# Main.net
KiCad netlist of a schematic drawn in Altium Designer
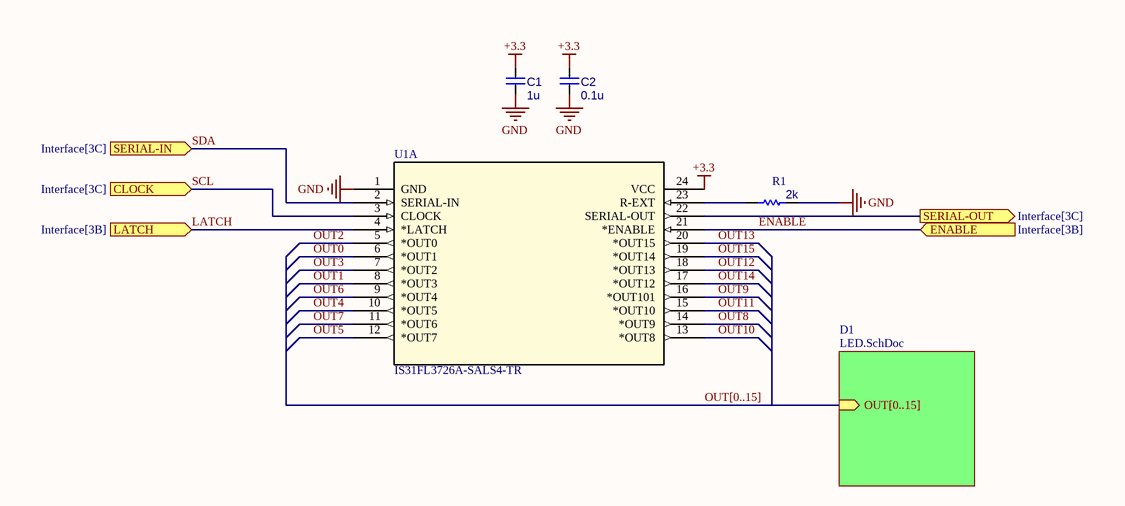
[diagram p0: Main.SchDoc]

(export (version "E")
  (design (tool "Eeschema 10.0.6"))
  (components
    (comp (ref "C1")
      (value "1u")
      (footprint "C0603B")
      (description "Non-polarized capacitor")
      (fields (field (name "Comment") "Capacitor"))
      (libsource (lib "Space Concordia") (part "Capacitor"))
    )
    (comp (ref "C2")
      (value "0.1u")
      (footprint "C0603B")
      (description "Non-polarized capacitor")
      (fields (field (name "Comment") "Capacitor"))
      (libsource (lib "Space Concordia") (part "Capacitor"))
    )
    (comp (ref "R1")
      (value "2k")
      (footprint "R0603B")
      (description "Resistor")
      (libsource (lib "Space Concordia") (part "Resistor"))
    )
    (comp (ref "U1")
      (value "IS31FL3726A-SALS4-TR")
      (footprint "SSOP-24_LMS")
      (description "LED Driver IC 16 Output Linear Shift Register No Dimming 25.2mA 24-eTSSOP")
      (libsource (lib "Space Concordia") (part "IS31FL3726A-SALS4-TR"))
    )
  )
  (nets
    (net (code "1") (name "+3.3") (class "Default")
      (node (ref "C1") (pin "1") (pinfunction "1_1") (pintype "passive"))
      (node (ref "C2") (pin "1") (pinfunction "1_1") (pintype "passive"))
      (node (ref "U1") (pin "24") (pinfunction "VCC_24") (pintype "power_in"))
    )
    (net (code "2") (name "/ENABLE") (class "Default")
      (node (ref "U1") (pin "21") (pinfunction "*ENABLE_21") (pintype "input"))
    )
    (net (code "3") (name "/LATCH") (class "Default")
      (node (ref "U1") (pin "4") (pinfunction "*LATCH_4") (pintype "input"))
    )
    (net (code "4") (name "/OUT0") (class "Default")
      (node (ref "U1") (pin "6") (pinfunction "*OUT1_6") (pintype "output"))
    )
    (net (code "5") (name "/OUT1") (class "Default")
      (node (ref "U1") (pin "8") (pinfunction "*OUT3_8") (pintype "output"))
    )
    (net (code "6") (name "/OUT2") (class "Default")
      (node (ref "U1") (pin "5") (pinfunction "*OUT0_5") (pintype "output"))
    )
    (net (code "7") (name "/OUT3") (class "Default")
      (node (ref "U1") (pin "7") (pinfunction "*OUT2_7") (pintype "output"))
    )
    (net (code "8") (name "/OUT4") (class "Default")
      (node (ref "U1") (pin "10") (pinfunction "*OUT5_10") (pintype "output"))
    )
    (net (code "9") (name "/OUT5") (class "Default")
      (node (ref "U1") (pin "12") (pinfunction "*OUT7_12") (pintype "output"))
    )
    (net (code "10") (name "/OUT6") (class "Default")
      (node (ref "U1") (pin "9") (pinfunction "*OUT4_9") (pintype "output"))
    )
    (net (code "11") (name "/OUT7") (class "Default")
      (node (ref "U1") (pin "11") (pinfunction "*OUT6_11") (pintype "output"))
    )
    (net (code "12") (name "/OUT8") (class "Default")
      (node (ref "U1") (pin "14") (pinfunction "*OUT9_14") (pintype "output"))
    )
    (net (code "13") (name "/OUT9") (class "Default")
      (node (ref "U1") (pin "16") (pinfunction "*OUT101_16") (pintype "output"))
    )
    (net (code "14") (name "/OUT10") (class "Default")
      (node (ref "U1") (pin "13") (pinfunction "*OUT8_13") (pintype "output"))
    )
    (net (code "15") (name "/OUT11") (class "Default")
      (node (ref "U1") (pin "15") (pinfunction "*OUT10_15") (pintype "output"))
    )
    (net (code "16") (name "/OUT12") (class "Default")
      (node (ref "U1") (pin "18") (pinfunction "*OUT13_18") (pintype "output"))
    )
    (net (code "17") (name "/OUT13") (class "Default")
      (node (ref "U1") (pin "20") (pinfunction "*OUT15_20") (pintype "output"))
    )
    (net (code "18") (name "/OUT14") (class "Default")
      (node (ref "U1") (pin "17") (pinfunction "*OUT12_17") (pintype "output"))
    )
    (net (code "19") (name "/OUT15") (class "Default")
      (node (ref "U1") (pin "19") (pinfunction "*OUT14_19") (pintype "output"))
    )
    (net (code "21") (name "/SCL") (class "Default")
      (node (ref "U1") (pin "3") (pinfunction "CLOCK_3") (pintype "input"))
    )
    (net (code "22") (name "/SDA") (class "Default")
      (node (ref "U1") (pin "2") (pinfunction "SERIAL-IN_2") (pintype "input"))
    )
    (net (code "23") (name "/SERIAL-OUT") (class "Default")
      (node (ref "U1") (pin "22") (pinfunction "SERIAL-OUT_22") (pintype "output"))
    )
    (net (code "24") (name "GND") (class "Default")
      (node (ref "C1") (pin "2") (pinfunction "2_2") (pintype "passive"))
      (node (ref "C2") (pin "2") (pinfunction "2_2") (pintype "passive"))
      (node (ref "R1") (pin "2") (pinfunction "2_2") (pintype "passive"))
      (node (ref "U1") (pin "1") (pinfunction "GND_1") (pintype "power_in"))
    )
    (net (code "25") (name "Net-(U1-R-EXT)") (class "Default")
      (node (ref "R1") (pin "1") (pinfunction "1_1") (pintype "passive"))
      (node (ref "U1") (pin "23") (pinfunction "R-EXT_23") (pintype "input"))
    )
  )
)
